# 328P-AU-RedBit.net
KiCad netlist of a schematic drawn in EAGLE
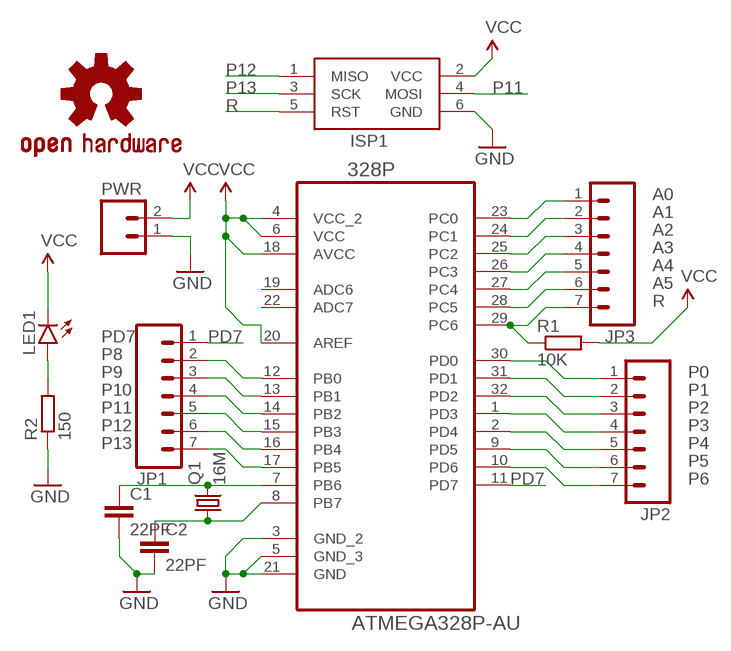
[diagram p0: schematic, sheet 1]

(export (version "E")
  (design (tool "Eeschema 10.0.6"))
  (components
    (comp (ref "328P")
      (value "ATMEGA328P-AU")
      (footprint "eagle-import:QFP80P900X900X120-32N")
      (libsource (lib "eagle-import") (part "ATMEGA328P-AU"))
    )
    (comp (ref "C1")
      (value "22PF")
      (footprint "eagle-import:C0805")
      (libsource (lib "eagle-import") (part "C-EUC0805"))
    )
    (comp (ref "C2")
      (value "22PF")
      (footprint "eagle-import:C0805")
      (libsource (lib "eagle-import") (part "C-EUC0805"))
    )
    (comp (ref "ISP1")
      (value "AVRISP-6")
      (footprint "eagle-import:AVRISP")
      (libsource (lib "eagle-import") (part "AVRISP-6"))
    )
    (comp (ref "JP1")
      (value "M07")
      (footprint "eagle-import:1X07")
      (libsource (lib "eagle-import") (part "M07"))
    )
    (comp (ref "JP2")
      (value "M07")
      (footprint "eagle-import:1X07")
      (libsource (lib "eagle-import") (part "M07"))
    )
    (comp (ref "JP3")
      (value "M07")
      (footprint "eagle-import:1X07")
      (libsource (lib "eagle-import") (part "M07"))
    )
    (comp (ref "LED1")
      (value "LED0603")
      (footprint "eagle-import:LED-0603")
      (libsource (lib "eagle-import") (part "LED0603"))
    )
    (comp (ref "LOGO1")
      (value "OSHW-LOGOS")
      (footprint "eagle-import:OSHW-LOGO-S")
      (libsource (lib "eagle-import") (part "OSHW-LOGOS"))
    )
    (comp (ref "PWR")
      (value "M02PTH")
      (footprint "eagle-import:1X02")
      (libsource (lib "eagle-import") (part "M02PTH"))
    )
    (comp (ref "Q1")
      (value "16M")
      (footprint "eagle-import:HC49_S")
      (libsource (lib "eagle-import") (part "CRYSTALHC49S"))
    )
    (comp (ref "R1")
      (value "10K")
      (footprint "eagle-import:R0805")
      (libsource (lib "eagle-import") (part "R-EU_R0805"))
    )
    (comp (ref "R2")
      (value "150")
      (footprint "eagle-import:R0805")
      (libsource (lib "eagle-import") (part "R-EU_R0805"))
    )
  )
  (nets
    (net (code "1") (name "/A0") (class "Default")
      (node (ref "328P") (pin "23") (pinfunction "PC0_23") (pintype "bidirectional"))
      (node (ref "JP3") (pin "1") (pinfunction "1_1") (pintype "passive"))
    )
    (net (code "2") (name "/A1") (class "Default")
      (node (ref "328P") (pin "24") (pinfunction "PC1_24") (pintype "bidirectional"))
      (node (ref "JP3") (pin "2") (pinfunction "2_2") (pintype "passive"))
    )
    (net (code "3") (name "/A2") (class "Default")
      (node (ref "328P") (pin "25") (pinfunction "PC2_25") (pintype "bidirectional"))
      (node (ref "JP3") (pin "3") (pinfunction "3_3") (pintype "passive"))
    )
    (net (code "4") (name "/A3") (class "Default")
      (node (ref "328P") (pin "26") (pinfunction "PC3_26") (pintype "bidirectional"))
      (node (ref "JP3") (pin "4") (pinfunction "4_4") (pintype "passive"))
    )
    (net (code "5") (name "/A4") (class "Default")
      (node (ref "328P") (pin "27") (pinfunction "PC4_27") (pintype "bidirectional"))
      (node (ref "JP3") (pin "5") (pinfunction "5_5") (pintype "passive"))
    )
    (net (code "6") (name "/A5") (class "Default")
      (node (ref "328P") (pin "28") (pinfunction "PC5_28") (pintype "bidirectional"))
      (node (ref "JP3") (pin "6") (pinfunction "6_6") (pintype "passive"))
    )
    (net (code "7") (name "/P0") (class "Default")
      (node (ref "328P") (pin "30") (pinfunction "PD0_30") (pintype "bidirectional"))
      (node (ref "JP2") (pin "1") (pinfunction "1_1") (pintype "passive"))
    )
    (net (code "8") (name "/P1") (class "Default")
      (node (ref "328P") (pin "31") (pinfunction "PD1_31") (pintype "bidirectional"))
      (node (ref "JP2") (pin "2") (pinfunction "2_2") (pintype "passive"))
    )
    (net (code "9") (name "/P2") (class "Default")
      (node (ref "328P") (pin "32") (pinfunction "PD2_32") (pintype "bidirectional"))
      (node (ref "JP2") (pin "3") (pinfunction "3_3") (pintype "passive"))
    )
    (net (code "10") (name "/P3") (class "Default")
      (node (ref "328P") (pin "1") (pinfunction "PD3_1") (pintype "bidirectional"))
      (node (ref "JP2") (pin "4") (pinfunction "4_4") (pintype "passive"))
    )
    (net (code "11") (name "/P4") (class "Default")
      (node (ref "328P") (pin "2") (pinfunction "PD4_2") (pintype "bidirectional"))
      (node (ref "JP2") (pin "5") (pinfunction "5_5") (pintype "passive"))
    )
    (net (code "12") (name "/P5") (class "Default")
      (node (ref "328P") (pin "9") (pinfunction "PD5_9") (pintype "bidirectional"))
      (node (ref "JP2") (pin "6") (pinfunction "6_6") (pintype "passive"))
    )
    (net (code "13") (name "/P6") (class "Default")
      (node (ref "328P") (pin "10") (pinfunction "PD6_10") (pintype "bidirectional"))
      (node (ref "JP2") (pin "7") (pinfunction "7_7") (pintype "passive"))
    )
    (net (code "14") (name "/P8") (class "Default")
      (node (ref "328P") (pin "12") (pinfunction "PB0_12") (pintype "bidirectional"))
      (node (ref "JP1") (pin "2") (pinfunction "2_2") (pintype "passive"))
    )
    (net (code "15") (name "/P9") (class "Default")
      (node (ref "328P") (pin "13") (pinfunction "PB1_13") (pintype "bidirectional"))
      (node (ref "JP1") (pin "3") (pinfunction "3_3") (pintype "passive"))
    )
    (net (code "16") (name "/P10") (class "Default")
      (node (ref "328P") (pin "14") (pinfunction "PB2_14") (pintype "bidirectional"))
      (node (ref "JP1") (pin "4") (pinfunction "4_4") (pintype "passive"))
    )
    (net (code "17") (name "/P11") (class "Default")
      (node (ref "328P") (pin "15") (pinfunction "PB3_15") (pintype "bidirectional"))
      (node (ref "ISP1") (pin "4") (pinfunction "MOSI_4") (pintype "output"))
      (node (ref "JP1") (pin "5") (pinfunction "5_5") (pintype "passive"))
    )
    (net (code "18") (name "/P12") (class "Default")
      (node (ref "328P") (pin "16") (pinfunction "PB4_16") (pintype "bidirectional"))
      (node (ref "ISP1") (pin "1") (pinfunction "MISO_1") (pintype "input"))
      (node (ref "JP1") (pin "6") (pinfunction "6_6") (pintype "passive"))
    )
    (net (code "19") (name "/P13") (class "Default")
      (node (ref "328P") (pin "17") (pinfunction "PB5_17") (pintype "bidirectional"))
      (node (ref "ISP1") (pin "3") (pinfunction "SCK_3") (pintype "output"))
      (node (ref "JP1") (pin "7") (pinfunction "7_7") (pintype "passive"))
    )
    (net (code "20") (name "/PD7") (class "Default")
      (node (ref "328P") (pin "11") (pinfunction "PD7_11") (pintype "bidirectional"))
      (node (ref "JP1") (pin "1") (pinfunction "1_1") (pintype "passive"))
    )
    (net (code "21") (name "/R") (class "Default")
      (node (ref "328P") (pin "29") (pinfunction "PC6_29") (pintype "bidirectional"))
      (node (ref "ISP1") (pin "5") (pinfunction "RST_5") (pintype "output"))
      (node (ref "JP3") (pin "7") (pinfunction "7_7") (pintype "passive"))
      (node (ref "R1") (pin "1") (pinfunction "1_1") (pintype "passive"))
    )
    (net (code "22") (name "GND") (class "Default")
      (node (ref "328P") (pin "21") (pinfunction "GND_21") (pintype "passive"))
      (node (ref "328P") (pin "3") (pinfunction "GND_2_3") (pintype "passive"))
      (node (ref "328P") (pin "5") (pinfunction "GND_3_5") (pintype "passive"))
      (node (ref "C1") (pin "2") (pinfunction "2_2") (pintype "passive"))
      (node (ref "C2") (pin "2") (pinfunction "2_2") (pintype "passive"))
      (node (ref "ISP1") (pin "6") (pinfunction "GND_6") (pintype "power_in"))
      (node (ref "PWR") (pin "1") (pinfunction "1_1") (pintype "passive"))
      (node (ref "R2") (pin "1") (pinfunction "1_1") (pintype "passive"))
    )
    (net (code "23") (name "Net-(328P-PB6)") (class "Default")
      (node (ref "328P") (pin "7") (pinfunction "PB6_7") (pintype "bidirectional"))
      (node (ref "C1") (pin "1") (pinfunction "1_1") (pintype "passive"))
      (node (ref "Q1") (pin "2") (pinfunction "2_2") (pintype "passive"))
    )
    (net (code "24") (name "Net-(328P-PB7)") (class "Default")
      (node (ref "328P") (pin "8") (pinfunction "PB7_8") (pintype "bidirectional"))
      (node (ref "C2") (pin "1") (pinfunction "1_1") (pintype "passive"))
      (node (ref "Q1") (pin "1") (pinfunction "1_1") (pintype "passive"))
    )
    (net (code "25") (name "Net-(LED1-PadA)") (class "Default")
      (node (ref "LED1") (pin "A") (pinfunction "A_A") (pintype "passive"))
      (node (ref "R2") (pin "2") (pinfunction "2_2") (pintype "passive"))
    )
    (net (code "26") (name "VCC") (class "Default")
      (node (ref "328P") (pin "18") (pinfunction "AVCC_18") (pintype "power_in"))
      (node (ref "328P") (pin "20") (pinfunction "AREF_20") (pintype "input"))
      (node (ref "328P") (pin "4") (pinfunction "VCC_2_4") (pintype "power_in"))
      (node (ref "328P") (pin "6") (pinfunction "VCC_6") (pintype "power_in"))
      (node (ref "ISP1") (pin "2") (pinfunction "VCC_2") (pintype "power_in"))
      (node (ref "LED1") (pin "C") (pinfunction "C_C") (pintype "passive"))
      (node (ref "PWR") (pin "2") (pinfunction "2_2") (pintype "passive"))
      (node (ref "R1") (pin "2") (pinfunction "2_2") (pintype "passive"))
    )
    (net (code "27") (name "unconnected-(328P-ADC6-Pad19)") (class "Default")
      (node (ref "328P") (pin "19") (pinfunction "ADC6_19") (pintype "input"))
    )
    (net (code "28") (name "unconnected-(328P-ADC7-Pad22)") (class "Default")
      (node (ref "328P") (pin "22") (pinfunction "ADC7_22") (pintype "input"))
    )
  )
)
